# Step_Stick.net
KiCad netlist of a schematic drawn in EAGLE
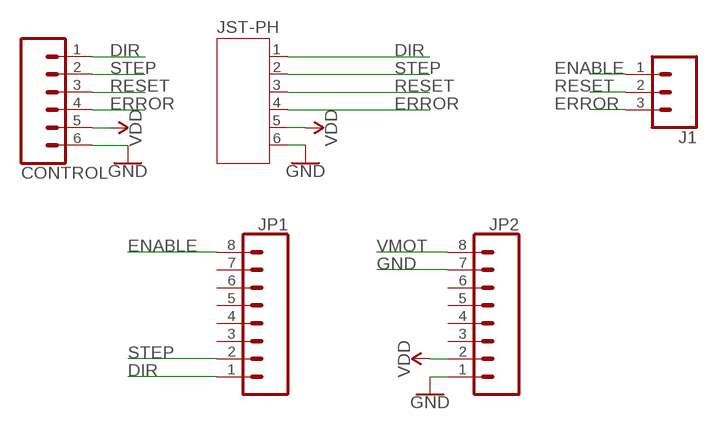
[diagram p0: schematic, sheet 1]

(export (version "E")
  (design (tool "Eeschema 10.0.6"))
  (components
    (comp (ref "CONTROL")
      (value "CONN_06NO_SILK_FEMALE_PTH")
      (footprint "eagle-import:1X06_NO_SILK")
      (libsource (lib "eagle-import") (part "CONN_06NO_SILK_FEMALE_PTH"))
    )
    (comp (ref "J1")
      (value "CONN_031X03_NO_SILK")
      (footprint "eagle-import:1X03_NO_SILK")
      (libsource (lib "eagle-import") (part "CONN_031X03_NO_SILK"))
    )
    (comp (ref "JP1")
      (value "CONN_08NO_SILK_FEMALE_PTH")
      (footprint "eagle-import:1X08_NO_SILK")
      (libsource (lib "eagle-import") (part "CONN_08NO_SILK_FEMALE_PTH"))
    )
    (comp (ref "JP2")
      (value "CONN_08NO_SILK_FEMALE_PTH")
      (footprint "eagle-import:1X08_NO_SILK")
      (libsource (lib "eagle-import") (part "CONN_08NO_SILK_FEMALE_PTH"))
    )
    (comp (ref "JST-PH")
      (value "JST-PH6")
      (footprint "eagle-import:JST-PH6")
      (libsource (lib "eagle-import") (part "JST-PH6"))
    )
  )
  (nets
    (net (code "1") (name "/DIR") (class "Default")
      (node (ref "CONTROL") (pin "1") (pinfunction "1_1") (pintype "passive"))
      (node (ref "JP1") (pin "1") (pinfunction "1_1") (pintype "passive"))
      (node (ref "JST-PH") (pin "1") (pinfunction "1_1") (pintype "passive"))
    )
    (net (code "2") (name "/ENABLE") (class "Default")
      (node (ref "J1") (pin "1") (pinfunction "1_1") (pintype "passive"))
      (node (ref "JP1") (pin "8") (pinfunction "8_8") (pintype "passive"))
    )
    (net (code "3") (name "/ERROR") (class "Default")
      (node (ref "CONTROL") (pin "4") (pinfunction "4_4") (pintype "passive"))
      (node (ref "J1") (pin "3") (pinfunction "3_3") (pintype "passive"))
      (node (ref "JST-PH") (pin "4") (pinfunction "4_4") (pintype "passive"))
    )
    (net (code "4") (name "/RESET") (class "Default")
      (node (ref "CONTROL") (pin "3") (pinfunction "3_3") (pintype "passive"))
      (node (ref "J1") (pin "2") (pinfunction "2_2") (pintype "passive"))
      (node (ref "JST-PH") (pin "3") (pinfunction "3_3") (pintype "passive"))
    )
    (net (code "5") (name "/STEP") (class "Default")
      (node (ref "CONTROL") (pin "2") (pinfunction "2_2") (pintype "passive"))
      (node (ref "JP1") (pin "2") (pinfunction "2_2") (pintype "passive"))
      (node (ref "JST-PH") (pin "2") (pinfunction "2_2") (pintype "passive"))
    )
    (net (code "6") (name "/VMOT") (class "Default")
      (node (ref "JP2") (pin "8") (pinfunction "8_8") (pintype "passive"))
    )
    (net (code "7") (name "GND") (class "Default")
      (node (ref "CONTROL") (pin "6") (pinfunction "6_6") (pintype "passive"))
      (node (ref "JP2") (pin "1") (pinfunction "1_1") (pintype "passive"))
      (node (ref "JP2") (pin "7") (pinfunction "7_7") (pintype "passive"))
      (node (ref "JST-PH") (pin "6") (pinfunction "6_6") (pintype "passive"))
    )
    (net (code "8") (name "VDD") (class "Default")
      (node (ref "CONTROL") (pin "5") (pinfunction "5_5") (pintype "passive"))
      (node (ref "JP2") (pin "2") (pinfunction "2_2") (pintype "passive"))
      (node (ref "JST-PH") (pin "5") (pinfunction "5_5") (pintype "passive"))
    )
    (net (code "9") (name "unconnected-(JP1-Pad3)") (class "Default")
      (node (ref "JP1") (pin "3") (pinfunction "3_3") (pintype "passive"))
    )
    (net (code "10") (name "unconnected-(JP1-Pad4)") (class "Default")
      (node (ref "JP1") (pin "4") (pinfunction "4_4") (pintype "passive"))
    )
    (net (code "11") (name "unconnected-(JP1-Pad5)") (class "Default")
      (node (ref "JP1") (pin "5") (pinfunction "5_5") (pintype "passive"))
    )
    (net (code "12") (name "unconnected-(JP1-Pad6)") (class "Default")
      (node (ref "JP1") (pin "6") (pinfunction "6_6") (pintype "passive"))
    )
    (net (code "13") (name "unconnected-(JP1-Pad7)") (class "Default")
      (node (ref "JP1") (pin "7") (pinfunction "7_7") (pintype "passive"))
    )
    (net (code "14") (name "unconnected-(JP2-Pad3)") (class "Default")
      (node (ref "JP2") (pin "3") (pinfunction "3_3") (pintype "passive"))
    )
    (net (code "15") (name "unconnected-(JP2-Pad4)") (class "Default")
      (node (ref "JP2") (pin "4") (pinfunction "4_4") (pintype "passive"))
    )
    (net (code "16") (name "unconnected-(JP2-Pad5)") (class "Default")
      (node (ref "JP2") (pin "5") (pinfunction "5_5") (pintype "passive"))
    )
    (net (code "17") (name "unconnected-(JP2-Pad6)") (class "Default")
      (node (ref "JP2") (pin "6") (pinfunction "6_6") (pintype "passive"))
    )
  )
)
